# isoamp.net
KiCad netlist of a schematic drawn in EAGLE
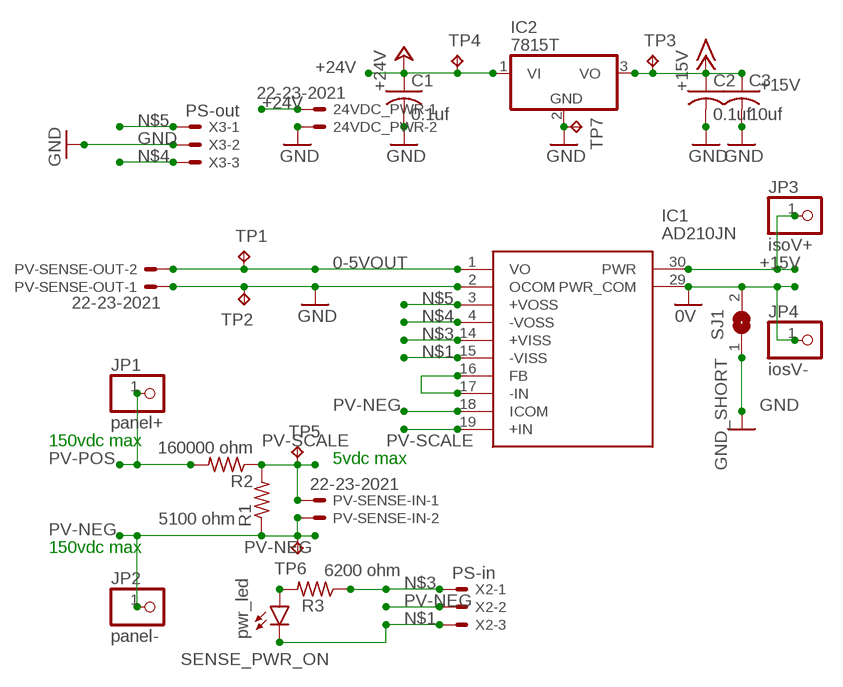
[diagram p0: schematic, sheet 1]

(export (version "E")
  (design (tool "Eeschema 10.0.6"))
  (components
    (comp (ref "24VDC_PWR")
      (value "22-23-2021")
      (footprint "eagle-import:22-23-2021")
      (fields (field (name "MF") "MOLEX"))
      (libsource (lib "eagle-import") (part "22-23-2021"))
    )
    (comp (ref "C1")
      (value "0.1uf")
      (footprint "eagle-import:C1206")
      (libsource (lib "eagle-import") (part "C-USC1206"))
    )
    (comp (ref "C2")
      (value "0.1uf")
      (footprint "eagle-import:C1206")
      (libsource (lib "eagle-import") (part "C-USC1206"))
    )
    (comp (ref "C3")
      (value "10uf")
      (footprint "eagle-import:C1206")
      (libsource (lib "eagle-import") (part "C-USC1206"))
    )
    (comp (ref "IC1")
      (value "AD210JN")
      (footprint "eagle-import:AD210_N_12")
      (fields (field (name "MOUSER_PART_NUMBER") "584-AD210JN"))
      (libsource (lib "eagle-import") (part "AD210JN"))
    )
    (comp (ref "IC2")
      (value "7815T")
      (footprint "eagle-import:TO220H")
      (libsource (lib "eagle-import") (part "78T15"))
    )
    (comp (ref "JP1")
      (value "panel+")
      (footprint "eagle-import:1X01")
      (libsource (lib "eagle-import") (part "PINHD-1X1"))
    )
    (comp (ref "JP2")
      (value "panel-")
      (footprint "eagle-import:1X01")
      (libsource (lib "eagle-import") (part "PINHD-1X1"))
    )
    (comp (ref "JP3")
      (value "isoV+")
      (footprint "eagle-import:1X01")
      (libsource (lib "eagle-import") (part "PINHD-1X1"))
    )
    (comp (ref "JP4")
      (value "iosV-")
      (footprint "eagle-import:1X01")
      (libsource (lib "eagle-import") (part "PINHD-1X1"))
    )
    (comp (ref "PV-SENSE-IN")
      (value "22-23-2021")
      (footprint "eagle-import:22-23-2021")
      (fields (field (name "MF") "MOLEX"))
      (libsource (lib "eagle-import") (part "22-23-2021"))
    )
    (comp (ref "PV-SENSE-OUT")
      (value "22-23-2021")
      (footprint "eagle-import:22-23-2021")
      (fields (field (name "MF") "MOLEX"))
      (libsource (lib "eagle-import") (part "22-23-2021"))
    )
    (comp (ref "R1")
      (value "5100 ohm")
      (footprint "eagle-import:M1206")
      (libsource (lib "eagle-import") (part "R-US_M1206"))
    )
    (comp (ref "R2")
      (value "160000 ohm")
      (footprint "eagle-import:0204_7")
      (libsource (lib "eagle-import") (part "R-US_0204/7"))
    )
    (comp (ref "R3")
      (value "6200 ohm")
      (footprint "eagle-import:M1206")
      (libsource (lib "eagle-import") (part "R-US_M1206"))
    )
    (comp (ref "SENSE_PWR_ON")
      (value "pwr_led")
      (footprint "eagle-import:CHIPLED_1206")
      (libsource (lib "eagle-import") (part "LEDCHIPLED_1206"))
    )
    (comp (ref "SJ1")
      (value "GND_SHORT")
      (footprint "eagle-import:SJW")
      (libsource (lib "eagle-import") (part "SJW"))
    )
    (comp (ref "TP1")
      (value "TPPAD1-13")
      (footprint "eagle-import:P1-13")
      (libsource (lib "eagle-import") (part "TPPAD1-13"))
    )
    (comp (ref "TP2")
      (value "TPPAD1-13")
      (footprint "eagle-import:P1-13")
      (libsource (lib "eagle-import") (part "TPPAD1-13"))
    )
    (comp (ref "TP3")
      (value "TPPAD1-13")
      (footprint "eagle-import:P1-13")
      (libsource (lib "eagle-import") (part "TPPAD1-13"))
    )
    (comp (ref "TP4")
      (value "TPPAD1-13")
      (footprint "eagle-import:P1-13")
      (libsource (lib "eagle-import") (part "TPPAD1-13"))
    )
    (comp (ref "TP5")
      (value "TPPAD1-13")
      (footprint "eagle-import:P1-13")
      (libsource (lib "eagle-import") (part "TPPAD1-13"))
    )
    (comp (ref "TP6")
      (value "TPPAD1-13")
      (footprint "eagle-import:P1-13")
      (libsource (lib "eagle-import") (part "TPPAD1-13"))
    )
    (comp (ref "TP7")
      (value "TPPAD1-13")
      (footprint "eagle-import:P1-13")
      (libsource (lib "eagle-import") (part "TPPAD1-13"))
    )
    (comp (ref "X2")
      (value "PS-in")
      (footprint "eagle-import:22-23-2031")
      (fields (field (name "MF") "MOLEX") (field (name "MPN") "22-23-2031"))
      (libsource (lib "eagle-import") (part "22-23-2031"))
    )
    (comp (ref "X3")
      (value "PS-out")
      (footprint "eagle-import:22-23-2031")
      (fields (field (name "MF") "MOLEX") (field (name "MPN") "22-23-2031"))
      (libsource (lib "eagle-import") (part "22-23-2031"))
    )
  )
  (nets
    (net (code "1") (name "+15V") (class "Default")
      (node (ref "C2") (pin "1") (pinfunction "1_1") (pintype "passive"))
      (node (ref "C3") (pin "1") (pinfunction "1_1") (pintype "passive"))
      (node (ref "IC1") (pin "30") (pinfunction "PWR_30") (pintype "bidirectional"))
      (node (ref "IC2") (pin "3") (pinfunction "VO_3") (pintype "passive"))
      (node (ref "JP3") (pin "1") (pinfunction "1_1") (pintype "passive"))
      (node (ref "TP3") (pin "TP") (pinfunction "TP_TP") (pintype "input"))
    )
    (net (code "2") (name "+24V") (class "Default")
      (node (ref "24VDC_PWR") (pin "1") (pinfunction "S_1") (pintype "passive"))
      (node (ref "C1") (pin "1") (pinfunction "1_1") (pintype "passive"))
      (node (ref "IC2") (pin "1") (pinfunction "VI_1") (pintype "input"))
      (node (ref "TP4") (pin "TP") (pinfunction "TP_TP") (pintype "input"))
    )
    (net (code "3") (name "/0-5VOUT") (class "Default")
      (node (ref "IC1") (pin "1") (pinfunction "VO_1") (pintype "bidirectional"))
      (node (ref "PV-SENSE-OUT") (pin "2") (pinfunction "S_2") (pintype "passive"))
      (node (ref "TP1") (pin "TP") (pinfunction "TP_TP") (pintype "input"))
    )
    (net (code "4") (name "/N$1") (class "Default")
      (node (ref "IC1") (pin "15") (pinfunction "-VISS_15") (pintype "bidirectional"))
      (node (ref "SENSE_PWR_ON") (pin "C") (pinfunction "C_C") (pintype "passive"))
      (node (ref "X2") (pin "3") (pinfunction "S_3") (pintype "passive"))
    )
    (net (code "5") (name "/N$3") (class "Default")
      (node (ref "IC1") (pin "14") (pinfunction "+VISS_14") (pintype "bidirectional"))
      (node (ref "R3") (pin "1") (pinfunction "1_1") (pintype "passive"))
      (node (ref "X2") (pin "1") (pinfunction "S_1") (pintype "passive"))
    )
    (net (code "6") (name "/N$4") (class "Default")
      (node (ref "IC1") (pin "4") (pinfunction "-VOSS_4") (pintype "bidirectional"))
      (node (ref "X3") (pin "3") (pinfunction "S_3") (pintype "passive"))
    )
    (net (code "7") (name "/N$5") (class "Default")
      (node (ref "IC1") (pin "3") (pinfunction "+VOSS_3") (pintype "bidirectional"))
      (node (ref "X3") (pin "1") (pinfunction "S_1") (pintype "passive"))
    )
    (net (code "8") (name "/PV-NEG") (class "Default")
      (node (ref "IC1") (pin "18") (pinfunction "ICOM_18") (pintype "bidirectional"))
      (node (ref "JP2") (pin "1") (pinfunction "1_1") (pintype "passive"))
      (node (ref "PV-SENSE-IN") (pin "2") (pinfunction "S_2") (pintype "passive"))
      (node (ref "R1") (pin "1") (pinfunction "1_1") (pintype "passive"))
      (node (ref "TP6") (pin "TP") (pinfunction "TP_TP") (pintype "input"))
      (node (ref "X2") (pin "2") (pinfunction "S_2") (pintype "passive"))
    )
    (net (code "9") (name "/PV-POS") (class "Default")
      (node (ref "JP1") (pin "1") (pinfunction "1_1") (pintype "passive"))
      (node (ref "R2") (pin "2") (pinfunction "2_2") (pintype "passive"))
    )
    (net (code "10") (name "/PV-SCALE") (class "Default")
      (node (ref "IC1") (pin "19") (pinfunction "+IN_19") (pintype "bidirectional"))
      (node (ref "PV-SENSE-IN") (pin "1") (pinfunction "S_1") (pintype "passive"))
      (node (ref "R1") (pin "2") (pinfunction "2_2") (pintype "passive"))
      (node (ref "R2") (pin "1") (pinfunction "1_1") (pintype "passive"))
      (node (ref "TP5") (pin "TP") (pinfunction "TP_TP") (pintype "input"))
    )
    (net (code "11") (name "0V") (class "Default")
      (node (ref "IC1") (pin "29") (pinfunction "PWR_COM_29") (pintype "bidirectional"))
      (node (ref "JP4") (pin "1") (pinfunction "1_1") (pintype "passive"))
      (node (ref "SJ1") (pin "2") (pinfunction "2_2") (pintype "passive"))
    )
    (net (code "12") (name "GND") (class "Default")
      (node (ref "24VDC_PWR") (pin "2") (pinfunction "S_2") (pintype "passive"))
      (node (ref "C1") (pin "2") (pinfunction "2_2") (pintype "passive"))
      (node (ref "C2") (pin "2") (pinfunction "2_2") (pintype "passive"))
      (node (ref "C3") (pin "2") (pinfunction "2_2") (pintype "passive"))
      (node (ref "IC1") (pin "2") (pinfunction "OCOM_2") (pintype "bidirectional"))
      (node (ref "IC2") (pin "2") (pinfunction "GND_2") (pintype "passive"))
      (node (ref "PV-SENSE-OUT") (pin "1") (pinfunction "S_1") (pintype "passive"))
      (node (ref "SJ1") (pin "1") (pinfunction "1_1") (pintype "passive"))
      (node (ref "TP2") (pin "TP") (pinfunction "TP_TP") (pintype "input"))
      (node (ref "TP7") (pin "TP") (pinfunction "TP_TP") (pintype "input"))
      (node (ref "X3") (pin "2") (pinfunction "S_2") (pintype "passive"))
    )
    (net (code "13") (name "Net-(IC1--IN)") (class "Default")
      (node (ref "IC1") (pin "16") (pinfunction "FB_16") (pintype "bidirectional"))
      (node (ref "IC1") (pin "17") (pinfunction "-IN_17") (pintype "bidirectional"))
    )
    (net (code "14") (name "Net-(R3-Pad2)") (class "Default")
      (node (ref "R3") (pin "2") (pinfunction "2_2") (pintype "passive"))
      (node (ref "SENSE_PWR_ON") (pin "A") (pinfunction "A_A") (pintype "passive"))
    )
  )
)
